# power_supply.net
KiCad netlist of a schematic drawn in Altium Designer
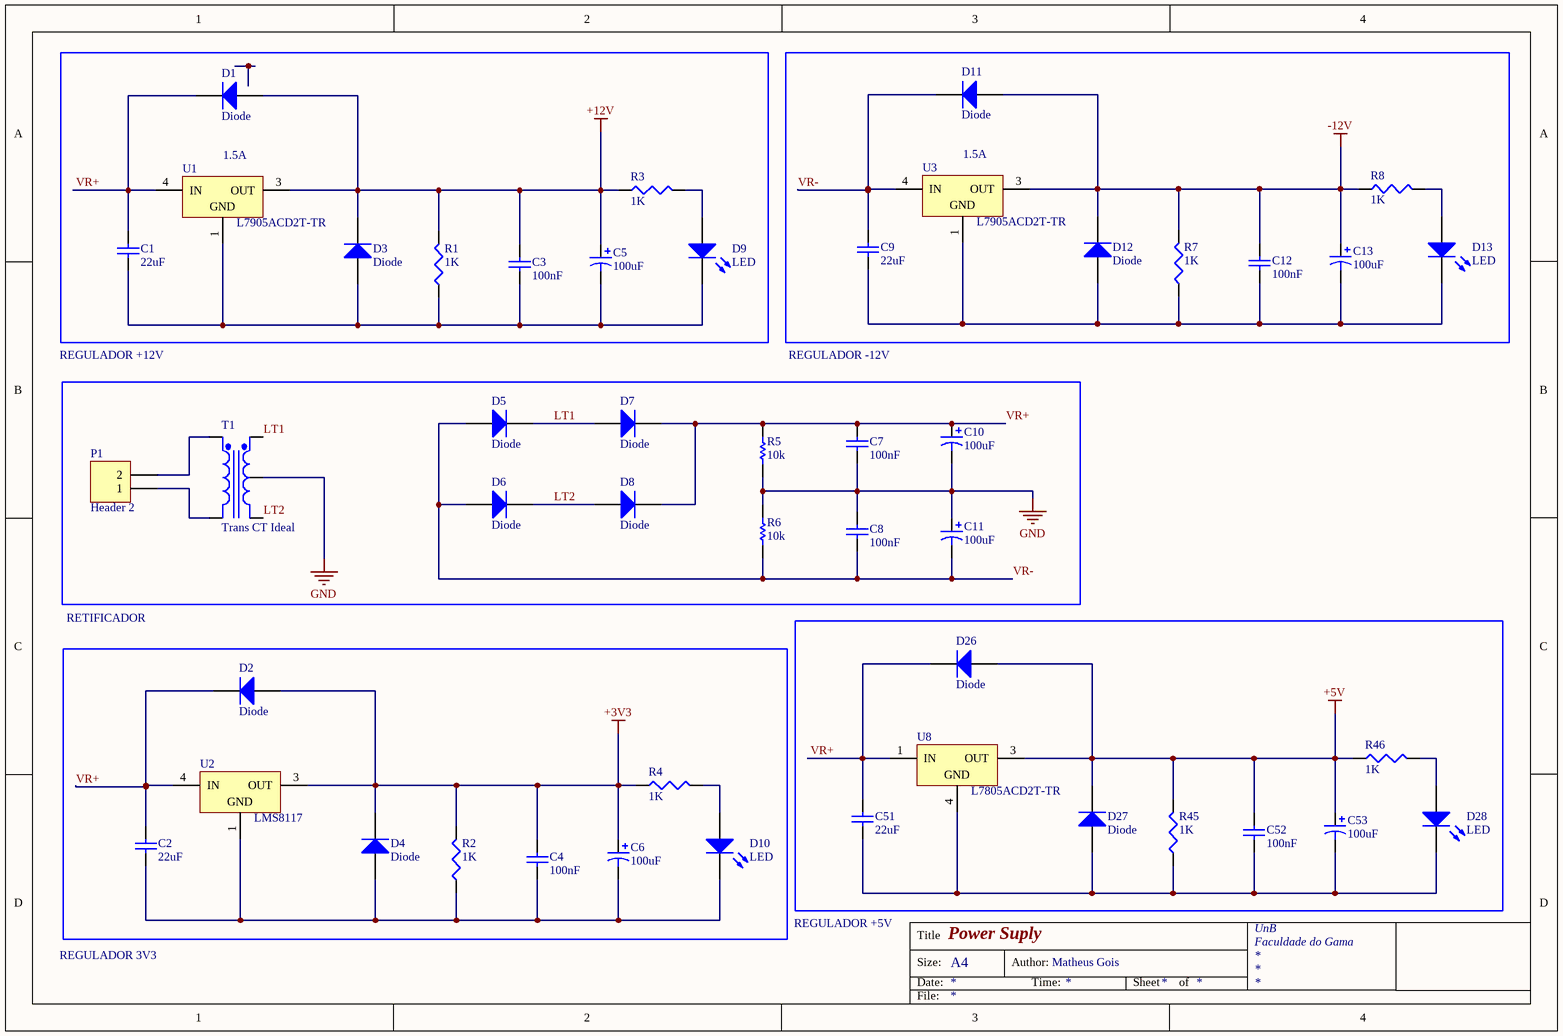
[diagram p0: power_supply.SchDoc]

(export (version "E")
  (design (tool "Eeschema 10.0.6"))
  (components
    (comp (ref "C1")
      (value "22uF")
      (footprint "C0603[0201]")
      (description "Cap Aluminum Polymer 22uF 20VDC 20% (6.3 X 5.9mm) SMD 0.06 Ohm 1450mA 5000h 105C T/R")
      (fields (field (name "MANUFACTURER PART NUMBER") "20SVPS22M") (field (name "TOLERANCE") "20%"))
      (libsource (lib "Basic Library") (part "C"))
    )
    (comp (ref "C2")
      (value "22uF")
      (footprint "C0603[0201]")
      (description "Cap Aluminum Polymer 22uF 20VDC 20% (6.3 X 5.9mm) SMD 0.06 Ohm 1450mA 5000h 105C T/R")
      (fields (field (name "MANUFACTURER PART NUMBER") "20SVPS22M") (field (name "TOLERANCE") "20%"))
      (libsource (lib "Basic Library") (part "C"))
    )
    (comp (ref "C3")
      (value "100nF")
      (footprint "C0603[0201]")
      (description "贴片陶瓷电容 0.1uF ±10% 50V X7R 0603")
      (fields (field (name "MANUFACTURER PART NUMBER") "C0603C104K5RACTU") (field (name "TOLERANCE") "10%"))
      (libsource (lib "Basic Library") (part "C"))
    )
    (comp (ref "C4")
      (value "100nF")
      (footprint "C0603[0201]")
      (description "贴片陶瓷电容 0.1uF ±10% 50V X7R 0603")
      (fields (field (name "MANUFACTURER PART NUMBER") "C0603C104K5RACTU") (field (name "TOLERANCE") "10%"))
      (libsource (lib "Basic Library") (part "C"))
    )
    (comp (ref "C5")
      (value "100uF")
      (footprint "Cap_Al_SMD_C6_6.6x6.6mm")
      (fields
        (field (name "MANUFACTURER PART NUMBER") "EMZA250ADA101MF80G")
        (field (name "TOLERANCE") "20%")
        (field (name "VOLTAGE") "25V")
      )
      (libsource (lib "Basic Library") (part "CP"))
    )
    (comp (ref "C6")
      (value "100uF")
      (footprint "Cap_Al_SMD_C6_6.6x6.6mm")
      (fields
        (field (name "MANUFACTURER PART NUMBER") "EMZA250ADA101MF80G")
        (field (name "TOLERANCE") "20%")
        (field (name "VOLTAGE") "25V")
      )
      (libsource (lib "Basic Library") (part "CP"))
    )
    (comp (ref "C7")
      (value "100nF")
      (footprint "C0603[0201]")
      (description "贴片陶瓷电容 0.1uF ±10% 50V X7R 0603")
      (fields (field (name "MANUFACTURER PART NUMBER") "C0603C104K5RACTU") (field (name "TOLERANCE") "10%"))
      (libsource (lib "Basic Library") (part "C"))
    )
    (comp (ref "C8")
      (value "100nF")
      (footprint "C0603[0201]")
      (description "贴片陶瓷电容 0.1uF ±10% 50V X7R 0603")
      (fields (field (name "MANUFACTURER PART NUMBER") "C0603C104K5RACTU") (field (name "TOLERANCE") "10%"))
      (libsource (lib "Basic Library") (part "C"))
    )
    (comp (ref "C9")
      (value "22uF")
      (footprint "C0603[0201]")
      (description "Cap Aluminum Polymer 22uF 20VDC 20% (6.3 X 5.9mm) SMD 0.06 Ohm 1450mA 5000h 105C T/R")
      (fields (field (name "MANUFACTURER PART NUMBER") "20SVPS22M") (field (name "TOLERANCE") "20%"))
      (libsource (lib "Basic Library") (part "C"))
    )
    (comp (ref "C10")
      (value "100uF")
      (footprint "Cap_Al_SMD_C6_6.6x6.6mm")
      (fields
        (field (name "MANUFACTURER PART NUMBER") "EMZA250ADA101MF80G")
        (field (name "TOLERANCE") "20%")
        (field (name "VOLTAGE") "25V")
      )
      (libsource (lib "Basic Library") (part "CP"))
    )
    (comp (ref "C11")
      (value "100uF")
      (footprint "Cap_Al_SMD_C6_6.6x6.6mm")
      (fields
        (field (name "MANUFACTURER PART NUMBER") "EMZA250ADA101MF80G")
        (field (name "TOLERANCE") "20%")
        (field (name "VOLTAGE") "25V")
      )
      (libsource (lib "Basic Library") (part "CP"))
    )
    (comp (ref "C12")
      (value "100nF")
      (footprint "C0603[0201]")
      (description "贴片陶瓷电容 0.1uF ±10% 50V X7R 0603")
      (fields (field (name "MANUFACTURER PART NUMBER") "C0603C104K5RACTU") (field (name "TOLERANCE") "10%"))
      (libsource (lib "Basic Library") (part "C"))
    )
    (comp (ref "C13")
      (value "100uF")
      (footprint "Cap_Al_SMD_C6_6.6x6.6mm")
      (fields
        (field (name "MANUFACTURER PART NUMBER") "EMZA250ADA101MF80G")
        (field (name "TOLERANCE") "20%")
        (field (name "VOLTAGE") "25V")
      )
      (libsource (lib "Basic Library") (part "CP"))
    )
    (comp (ref "C51")
      (value "22uF")
      (footprint "C0603[0201]")
      (description "Cap Aluminum Polymer 22uF 20VDC 20% (6.3 X 5.9mm) SMD 0.06 Ohm 1450mA 5000h 105C T/R")
      (fields (field (name "MANUFACTURER PART NUMBER") "20SVPS22M") (field (name "TOLERANCE") "20%"))
      (libsource (lib "Basic Library") (part "C"))
    )
    (comp (ref "C52")
      (value "100nF")
      (footprint "C0603[0201]")
      (description "贴片陶瓷电容 0.1uF ±10% 50V X7R 0603")
      (fields (field (name "MANUFACTURER PART NUMBER") "C0603C104K5RACTU") (field (name "TOLERANCE") "10%"))
      (libsource (lib "Basic Library") (part "C"))
    )
    (comp (ref "C53")
      (value "100uF")
      (footprint "Cap_Al_SMD_C6_6.6x6.6mm")
      (fields
        (field (name "MANUFACTURER PART NUMBER") "EMZA250ADA101MF80G")
        (field (name "TOLERANCE") "20%")
        (field (name "VOLTAGE") "25V")
      )
      (libsource (lib "Basic Library") (part "CP"))
    )
    (comp (ref "D1")
      (value "Diode")
      (footprint "SMC")
      (description "VR=100V IF=200mA")
      (fields
        (field (name "MANUFACTURER") "ON Semiconductor / Fairchild")
        (field (name "MANUFACTURER PART NUMBER") "FDLL4148")
        (field (name "PUBLISHER") "Altium Limited")
      )
      (libsource (lib "Miscellaneous Devices") (part "Diode"))
    )
    (comp (ref "D2")
      (value "Diode")
      (footprint "SMC")
      (description "VR=100V IF=200mA")
      (fields
        (field (name "MANUFACTURER") "ON Semiconductor / Fairchild")
        (field (name "MANUFACTURER PART NUMBER") "FDLL4148")
        (field (name "PUBLISHER") "Altium Limited")
      )
      (libsource (lib "Miscellaneous Devices") (part "Diode"))
    )
    (comp (ref "D3")
      (value "Diode")
      (footprint "SMC")
      (description "Standard Rectifier 1000V SOD-123")
      (fields
        (field (name "MANUFACTURER") "Sangdest Microelectronics")
        (field (name "MANUFACTURER PART NUMBER") "1N4007FLTR")
        (field (name "PUBLISHER") "Altium Limited")
      )
      (libsource (lib "Miscellaneous Devices") (part "Diode"))
    )
    (comp (ref "D4")
      (value "Diode")
      (footprint "SMC")
      (description "Standard Rectifier 1000V SOD-123")
      (fields
        (field (name "MANUFACTURER") "Sangdest Microelectronics")
        (field (name "MANUFACTURER PART NUMBER") "1N4007FLTR")
        (field (name "PUBLISHER") "Altium Limited")
      )
      (libsource (lib "Miscellaneous Devices") (part "Diode"))
    )
    (comp (ref "D5")
      (value "Diode")
      (footprint "SMC")
      (description "Standard Rectifier 1000V SOD-123")
      (fields
        (field (name "MANUFACTURER") "Sangdest Microelectronics")
        (field (name "MANUFACTURER PART NUMBER") "1N4007FLTR")
        (field (name "PUBLISHER") "Altium Limited")
      )
      (libsource (lib "Miscellaneous Devices") (part "Diode"))
    )
    (comp (ref "D6")
      (value "Diode")
      (footprint "SMC")
      (description "Standard Rectifier 1000V SOD-123")
      (fields
        (field (name "MANUFACTURER") "Sangdest Microelectronics")
        (field (name "MANUFACTURER PART NUMBER") "1N4007FLTR")
        (field (name "PUBLISHER") "Altium Limited")
      )
      (libsource (lib "Miscellaneous Devices") (part "Diode"))
    )
    (comp (ref "D7")
      (value "Diode")
      (footprint "SMC")
      (description "Standard Rectifier 1000V SOD-123")
      (fields
        (field (name "MANUFACTURER") "Sangdest Microelectronics")
        (field (name "MANUFACTURER PART NUMBER") "1N4007FLTR")
        (field (name "PUBLISHER") "Altium Limited")
      )
      (libsource (lib "Miscellaneous Devices") (part "Diode"))
    )
    (comp (ref "D8")
      (value "Diode")
      (footprint "SMC")
      (description "Standard Rectifier 1000V SOD-123")
      (fields
        (field (name "MANUFACTURER") "Sangdest Microelectronics")
        (field (name "MANUFACTURER PART NUMBER") "1N4007FLTR")
        (field (name "PUBLISHER") "Altium Limited")
      )
      (libsource (lib "Miscellaneous Devices") (part "Diode"))
    )
    (comp (ref "D9")
      (value "LED")
      (footprint "LED-0603-G")
      (description "0603(H=0.9mm) 绿色 λD=569nm VR=5V VF=2.1V~2.6V IF=20mA PD=100mW")
      (fields (field (name "MANUFACTURER PART NUMBER") "LTST-C190GKT") (field (name "VOLTAGE") "2V"))
      (libsource (lib "Basic Library") (part "LED"))
    )
    (comp (ref "D10")
      (value "LED")
      (footprint "LED-0603-G")
      (description "0603(H=0.9mm) 绿色 λD=569nm VR=5V VF=2.1V~2.6V IF=20mA PD=100mW")
      (fields (field (name "MANUFACTURER PART NUMBER") "LTST-C190GKT") (field (name "VOLTAGE") "2V"))
      (libsource (lib "Basic Library") (part "LED"))
    )
    (comp (ref "D11")
      (value "Diode")
      (footprint "SMC")
      (description "VR=100V IF=200mA")
      (fields
        (field (name "MANUFACTURER") "ON Semiconductor / Fairchild")
        (field (name "MANUFACTURER PART NUMBER") "FDLL4148")
        (field (name "PUBLISHER") "Altium Limited")
      )
      (libsource (lib "Miscellaneous Devices") (part "Diode"))
    )
    (comp (ref "D12")
      (value "Diode")
      (footprint "SMC")
      (description "Standard Rectifier 1000V SOD-123")
      (fields
        (field (name "MANUFACTURER") "Sangdest Microelectronics")
        (field (name "MANUFACTURER PART NUMBER") "1N4007FLTR")
        (field (name "PUBLISHER") "Altium Limited")
      )
      (libsource (lib "Miscellaneous Devices") (part "Diode"))
    )
    (comp (ref "D13")
      (value "LED")
      (footprint "LED-0603-G")
      (description "0603(H=0.9mm) 绿色 λD=569nm VR=5V VF=2.1V~2.6V IF=20mA PD=100mW")
      (fields (field (name "MANUFACTURER PART NUMBER") "LTST-C190GKT") (field (name "VOLTAGE") "2V"))
      (libsource (lib "Basic Library") (part "LED"))
    )
    (comp (ref "D26")
      (value "Diode")
      (footprint "SMC")
      (description "VR=100V IF=200mA")
      (fields
        (field (name "MANUFACTURER") "ON Semiconductor / Fairchild")
        (field (name "MANUFACTURER PART NUMBER") "FDLL4148")
        (field (name "PUBLISHER") "Altium Limited")
      )
      (libsource (lib "Miscellaneous Devices") (part "Diode"))
    )
    (comp (ref "D27")
      (value "Diode")
      (footprint "SMC")
      (description "Standard Rectifier 1000V SOD-123")
      (fields
        (field (name "MANUFACTURER") "Sangdest Microelectronics")
        (field (name "MANUFACTURER PART NUMBER") "1N4007FLTR")
        (field (name "PUBLISHER") "Altium Limited")
      )
      (libsource (lib "Miscellaneous Devices") (part "Diode"))
    )
    (comp (ref "D28")
      (value "LED")
      (footprint "LED-0603-G")
      (description "0603(H=0.9mm) 绿色 λD=569nm VR=5V VF=2.1V~2.6V IF=20mA PD=100mW")
      (fields (field (name "MANUFACTURER PART NUMBER") "LTST-C190GKT") (field (name "VOLTAGE") "2V"))
      (libsource (lib "Basic Library") (part "LED"))
    )
    (comp (ref "P1")
      (value "Header 2")
      (footprint "HDR1X2")
      (description "间距5.08mm 2pin 母座 12A 320V 弯插 封边")
      (fields
        (field (name "MANUFACTURER") "Phoenix Contact")
        (field (name "MANUFACTURER PART NUMBER") "1757242")
        (field (name "PUBLISHER") "Altium Limited")
      )
      (libsource (lib "Miscellaneous Connectors") (part "Header 2"))
    )
    (comp (ref "R1")
      (value "1K")
      (footprint "RESC6332")
      (description "Res Metal Strip 1206 0.001 Ohm 1% 0.25W(1/4W) ±275ppm/C Sulfur Resistant Pad SMD Automotive T/R")
      (fields
        (field (name "MANUFACTURER") "Vishay")
        (field (name "MANUFACTURER PART NUMBER") "WSL12061L000FEA")
        (field (name "PUBLISHER") "Altium Limited")
      )
      (libsource (lib "Miscellaneous Devices") (part "Res3"))
    )
    (comp (ref "R2")
      (value "1K")
      (footprint "RESC6332")
      (description "Res Metal Strip 1206 0.001 Ohm 1% 0.25W(1/4W) ±275ppm/C Sulfur Resistant Pad SMD Automotive T/R")
      (fields
        (field (name "MANUFACTURER") "Vishay")
        (field (name "MANUFACTURER PART NUMBER") "WSL12061L000FEA")
        (field (name "PUBLISHER") "Altium Limited")
      )
      (libsource (lib "Miscellaneous Devices") (part "Res3"))
    )
    (comp (ref "R3")
      (value "1K")
      (footprint "12Z-2010")
      (description "Res Metal Strip 1206 0.001 Ohm 1% 0.25W(1/4W) ±275ppm/C Sulfur Resistant Pad SMD Automotive T/R")
      (fields
        (field (name "MANUFACTURER") "Vishay")
        (field (name "MANUFACTURER PART NUMBER") "WSL12061L000FEA")
        (field (name "PUBLISHER") "Altium Limited")
      )
      (libsource (lib "Miscellaneous Devices") (part "Res3"))
    )
    (comp (ref "R4")
      (value "1K")
      (footprint "12Z-2010")
      (description "Res Metal Strip 1206 0.001 Ohm 1% 0.25W(1/4W) ±275ppm/C Sulfur Resistant Pad SMD Automotive T/R")
      (fields
        (field (name "MANUFACTURER") "Vishay")
        (field (name "MANUFACTURER PART NUMBER") "WSL12061L000FEA")
        (field (name "PUBLISHER") "Altium Limited")
      )
      (libsource (lib "Miscellaneous Devices") (part "Res3"))
    )
    (comp (ref "R5")
      (value "10k")
      (footprint "R1608[0603]")
      (description "Res, 10K, 0.01%, 0.25W, 1206, Metal Foil")
      (fields (field (name "MANUFACTURER PART NUMBER") "Y163010K0000T9R") (field (name "TOLERANCE") "0.01%"))
      (libsource (lib "Basic Library") (part "R"))
    )
    (comp (ref "R6")
      (value "10k")
      (footprint "R1608[0603]")
      (description "Res, 10K, 0.01%, 0.25W, 1206, Metal Foil")
      (fields (field (name "MANUFACTURER PART NUMBER") "Y163010K0000T9R") (field (name "TOLERANCE") "0.01%"))
      (libsource (lib "Basic Library") (part "R"))
    )
    (comp (ref "R7")
      (value "1K")
      (footprint "RESC6332")
      (description "Res Metal Strip 1206 0.001 Ohm 1% 0.25W(1/4W) ±275ppm/C Sulfur Resistant Pad SMD Automotive T/R")
      (fields
        (field (name "MANUFACTURER") "Vishay")
        (field (name "MANUFACTURER PART NUMBER") "WSL12061L000FEA")
        (field (name "PUBLISHER") "Altium Limited")
      )
      (libsource (lib "Miscellaneous Devices") (part "Res3"))
    )
    (comp (ref "R8")
      (value "1K")
      (footprint "12Z-2010")
      (description "Res Metal Strip 1206 0.001 Ohm 1% 0.25W(1/4W) ±275ppm/C Sulfur Resistant Pad SMD Automotive T/R")
      (fields
        (field (name "MANUFACTURER") "Vishay")
        (field (name "MANUFACTURER PART NUMBER") "WSL12061L000FEA")
        (field (name "PUBLISHER") "Altium Limited")
      )
      (libsource (lib "Miscellaneous Devices") (part "Res3"))
    )
    (comp (ref "R45")
      (value "1K")
      (footprint "RESC6332")
      (description "Res Metal Strip 1206 0.001 Ohm 1% 0.25W(1/4W) ±275ppm/C Sulfur Resistant Pad SMD Automotive T/R")
      (fields
        (field (name "MANUFACTURER") "Vishay")
        (field (name "MANUFACTURER PART NUMBER") "WSL12061L000FEA")
        (field (name "PUBLISHER") "Altium Limited")
      )
      (libsource (lib "Miscellaneous Devices") (part "Res3"))
    )
    (comp (ref "R46")
      (value "1K")
      (footprint "12Z-2010")
      (description "Res Metal Strip 1206 0.001 Ohm 1% 0.25W(1/4W) ±275ppm/C Sulfur Resistant Pad SMD Automotive T/R")
      (fields
        (field (name "MANUFACTURER") "Vishay")
        (field (name "MANUFACTURER PART NUMBER") "WSL12061L000FEA")
        (field (name "PUBLISHER") "Altium Limited")
      )
      (libsource (lib "Miscellaneous Devices") (part "Res3"))
    )
    (comp (ref "T1")
      (value "Trans CT Ideal")
      (description "Center-Tapped Transformer (Ideal)")
      (libsource (lib "Basic Library") (part "Trans CT Ideal"))
    )
    (comp (ref "U1")
      (value "L7905ACD2T-TR")
      (footprint "TO-263_N")
      (description "L7912 Series 1.5 A -12 V Fixed Output SMT Negative Voltage Regulator - D2PAK")
      (fields
        (field (name "MANUFACTURER") "STMicroelectronics")
        (field (name "MANUFACTURER PART NUMBER") "L7912CD2T-TR")
        (field (name "OUTPUT CURRENT") "1.5A")
      )
      (libsource (lib "STMicroelectronics Power Management Linear Regulator") (part "L7905ACD2T-TR"))
    )
    (comp (ref "U2")
      (value "LMS8117")
      (footprint "TO-263_N")
      (description "1-A, 15-V, linear voltage regulator from 0°C to 125°C 3-TO-252 0 to 125")
      (fields (field (name "PARTNUMBER") "L7905ACD2T-TR") (field (name "MANUFACTURER") "STMicroelectronics"))
      (libsource (lib "STMicroelectronics Power Management Linear Regulator") (part "L7905ACD2T-TR"))
    )
    (comp (ref "U3")
      (value "L7905ACD2T-TR")
      (footprint "TO-263_N")
      (description "L7912 Series 1.5 A -12 V Fixed Output SMT Negative Voltage Regulator - D2PAK")
      (fields
        (field (name "MANUFACTURER") "STMicroelectronics")
        (field (name "MANUFACTURER PART NUMBER") "L7912CD2T-TR")
        (field (name "OUTPUT CURRENT") "1.5A")
      )
      (libsource (lib "STMicroelectronics Power Management Linear Regulator") (part "L7905ACD2T-TR"))
    )
    (comp (ref "U8")
      (value "L7805ACD2T-TR")
      (footprint "TO-263_N")
      (description "Positive Voltage Regulator, 3-Pin D2PAK, Tape and Reel")
      (libsource (lib "STMicroelectronics Power Management Linear Regulator") (part "L7805ACD2T-TR"))
    )
  )
  (nets
    (net (code "1") (name "+3V3") (class "Default")
      (node (ref "C4") (pin "2") (pinfunction "2_2") (pintype "passive"))
      (node (ref "C6") (pin "1") (pinfunction "1_1") (pintype "passive"))
      (node (ref "D2") (pin "1") (pinfunction "A_1") (pintype "passive"))
      (node (ref "D4") (pin "2") (pinfunction "K_2") (pintype "passive"))
      (node (ref "R2") (pin "2") (pinfunction "2_2") (pintype "passive"))
      (node (ref "R4") (pin "1") (pinfunction "1_1") (pintype "passive"))
      (node (ref "U2") (pin "3") (pinfunction "OUT_3") (pintype "power_in"))
    )
    (net (code "2") (name "+5V") (class "Default")
      (node (ref "C52") (pin "2") (pinfunction "2_2") (pintype "passive"))
      (node (ref "C53") (pin "1") (pinfunction "1_1") (pintype "passive"))
      (node (ref "D26") (pin "1") (pinfunction "A_1") (pintype "passive"))
      (node (ref "D27") (pin "2") (pinfunction "K_2") (pintype "passive"))
      (node (ref "R45") (pin "2") (pinfunction "2_2") (pintype "passive"))
      (node (ref "R46") (pin "1") (pinfunction "1_1") (pintype "passive"))
      (node (ref "U8") (pin "3") (pinfunction "OUT_3") (pintype "power_in"))
    )
    (net (code "3") (name "+12V") (class "Default")
      (node (ref "C3") (pin "2") (pinfunction "2_2") (pintype "passive"))
      (node (ref "C5") (pin "1") (pinfunction "1_1") (pintype "passive"))
      (node (ref "D1") (pin "1") (pinfunction "A_1") (pintype "passive"))
      (node (ref "D3") (pin "2") (pinfunction "K_2") (pintype "passive"))
      (node (ref "R1") (pin "2") (pinfunction "2_2") (pintype "passive"))
      (node (ref "R3") (pin "1") (pinfunction "1_1") (pintype "passive"))
      (node (ref "U1") (pin "3") (pinfunction "OUT_3") (pintype "power_in"))
    )
    (net (code "4") (name "-12V") (class "Default")
      (node (ref "C12") (pin "2") (pinfunction "2_2") (pintype "passive"))
      (node (ref "C13") (pin "1") (pinfunction "1_1") (pintype "passive"))
      (node (ref "D11") (pin "1") (pinfunction "A_1") (pintype "passive"))
      (node (ref "D12") (pin "2") (pinfunction "K_2") (pintype "passive"))
      (node (ref "R7") (pin "2") (pinfunction "2_2") (pintype "passive"))
      (node (ref "R8") (pin "1") (pinfunction "1_1") (pintype "passive"))
      (node (ref "U3") (pin "3") (pinfunction "OUT_3") (pintype "power_in"))
    )
    (net (code "5") (name "/LT1") (class "Default")
      (node (ref "D5") (pin "2") (pinfunction "K_2") (pintype "passive"))
      (node (ref "D7") (pin "1") (pinfunction "A_1") (pintype "passive"))
      (node (ref "T1") (pin "3") (pinfunction "Sec+_3") (pintype "passive"))
    )
    (net (code "6") (name "/LT2") (class "Default")
      (node (ref "D6") (pin "2") (pinfunction "K_2") (pintype "passive"))
      (node (ref "D8") (pin "1") (pinfunction "A_1") (pintype "passive"))
      (node (ref "T1") (pin "5") (pinfunction "Sec-_5") (pintype "passive"))
    )
    (net (code "7") (name "/VR+") (class "Default")
      (node (ref "C1") (pin "2") (pinfunction "2_2") (pintype "passive"))
      (node (ref "C10") (pin "1") (pinfunction "1_1") (pintype "passive"))
      (node (ref "C2") (pin "2") (pinfunction "2_2") (pintype "passive"))
      (node (ref "C51") (pin "2") (pinfunction "2_2") (pintype "passive"))
      (node (ref "C7") (pin "2") (pinfunction "2_2") (pintype "passive"))
      (node (ref "D1") (pin "2") (pinfunction "K_2") (pintype "passive"))
      (node (ref "D2") (pin "2") (pinfunction "K_2") (pintype "passive"))
      (node (ref "D26") (pin "2") (pinfunction "K_2") (pintype "passive"))
      (node (ref "D7") (pin "2") (pinfunction "K_2") (pintype "passive"))
      (node (ref "D8") (pin "2") (pinfunction "K_2") (pintype "passive"))
      (node (ref "R5") (pin "2") (pinfunction "2_2") (pintype "passive"))
      (node (ref "U1") (pin "4") (pinfunction "IN_4") (pintype "power_in"))
      (node (ref "U2") (pin "4") (pinfunction "IN_4") (pintype "power_in"))
      (node (ref "U8") (pin "1") (pinfunction "IN_1") (pintype "power_in"))
    )
    (net (code "8") (name "/VR-") (class "Default")
      (node (ref "C11") (pin "2") (pinfunction "2_2") (pintype "passive"))
      (node (ref "C8") (pin "1") (pinfunction "1_1") (pintype "passive"))
      (node (ref "C9") (pin "2") (pinfunction "2_2") (pintype "passive"))
      (node (ref "D11") (pin "2") (pinfunction "K_2") (pintype "passive"))
      (node (ref "D5") (pin "1") (pinfunction "A_1") (pintype "passive"))
      (node (ref "D6") (pin "1") (pinfunction "A_1") (pintype "passive"))
      (node (ref "R6") (pin "1") (pinfunction "1_1") (pintype "passive"))
      (node (ref "U3") (pin "4") (pinfunction "IN_4") (pintype "power_in"))
    )
    (net (code "9") (name "GND") (class "Default")
      (node (ref "C10") (pin "2") (pinfunction "2_2") (pintype "passive"))
      (node (ref "C11") (pin "1") (pinfunction "1_1") (pintype "passive"))
      (node (ref "C7") (pin "1") (pinfunction "1_1") (pintype "passive"))
      (node (ref "C8") (pin "2") (pinfunction "2_2") (pintype "passive"))
      (node (ref "R5") (pin "1") (pinfunction "1_1") (pintype "passive"))
      (node (ref "R6") (pin "2") (pinfunction "2_2") (pintype "passive"))
      (node (ref "T1") (pin "4") (pinfunction "SecCT_4") (pintype "passive"))
    )
    (net (code "10") (name "Net-(D3-A)") (class "Default")
      (node (ref "C1") (pin "1") (pinfunction "1_1") (pintype "passive"))
      (node (ref "C3") (pin "1") (pinfunction "1_1") (pintype "passive"))
      (node (ref "C5") (pin "2") (pinfunction "2_2") (pintype "passive"))
      (node (ref "D3") (pin "1") (pinfunction "A_1") (pintype "passive"))
      (node (ref "D9") (pin "2") (pinfunction "K_2") (pintype "passive"))
      (node (ref "R1") (pin "1") (pinfunction "1_1") (pintype "passive"))
      (node (ref "U1") (pin "1") (pinfunction "GND_1") (pintype "power_in"))
    )
    (net (code "11") (name "Net-(D9-A)") (class "Default")
      (node (ref "D9") (pin "1") (pinfunction "A_1") (pintype "passive"))
      (node (ref "R3") (pin "2") (pinfunction "2_2") (pintype "passive"))
    )
    (net (code "12") (name "Net-(D10-A)") (class "Default")
      (node (ref "D10") (pin "1") (pinfunction "A_1") (pintype "passive"))
      (node (ref "R4") (pin "2") (pinfunction "2_2") (pintype "passive"))
    )
    (net (code "13") (name "Net-(D10-K)") (class "Default")
      (node (ref "C2") (pin "1") (pinfunction "1_1") (pintype "passive"))
      (node (ref "C4") (pin "1") (pinfunction "1_1") (pintype "passive"))
      (node (ref "C6") (pin "2") (pinfunction "2_2") (pintype "passive"))
      (node (ref "D10") (pin "2") (pinfunction "K_2") (pintype "passive"))
      (node (ref "D4") (pin "1") (pinfunction "A_1") (pintype "passive"))
      (node (ref "R2") (pin "1") (pinfunction "1_1") (pintype "passive"))
      (node (ref "U2") (pin "1") (pinfunction "GND_1") (pintype "power_in"))
    )
    (net (code "14") (name "Net-(D12-A)") (class "Default")
      (node (ref "C12") (pin "1") (pinfunction "1_1") (pintype "passive"))
      (node (ref "C13") (pin "2") (pinfunction "2_2") (pintype "passive"))
      (node (ref "C9") (pin "1") (pinfunction "1_1") (pintype "passive"))
      (node (ref "D12") (pin "1") (pinfunction "A_1") (pintype "passive"))
      (node (ref "D13") (pin "2") (pinfunction "K_2") (pintype "passive"))
      (node (ref "R7") (pin "1") (pinfunction "1_1") (pintype "passive"))
      (node (ref "U3") (pin "1") (pinfunction "GND_1") (pintype "power_in"))
    )
    (net (code "15") (name "Net-(D13-A)") (class "Default")
      (node (ref "D13") (pin "1") (pinfunction "A_1") (pintype "passive"))
      (node (ref "R8") (pin "2") (pinfunction "2_2") (pintype "passive"))
    )
    (net (code "16") (name "Net-(D27-A)") (class "Default")
      (node (ref "C51") (pin "1") (pinfunction "1_1") (pintype "passive"))
      (node (ref "C52") (pin "1") (pinfunction "1_1") (pintype "passive"))
      (node (ref "C53") (pin "2") (pinfunction "2_2") (pintype "passive"))
      (node (ref "D27") (pin "1") (pinfunction "A_1") (pintype "passive"))
      (node (ref "D28") (pin "2") (pinfunction "K_2") (pintype "passive"))
      (node (ref "R45") (pin "1") (pinfunction "1_1") (pintype "passive"))
      (node (ref "U8") (pin "4") (pinfunction "GND_4") (pintype "power_in"))
    )
    (net (code "17") (name "Net-(D28-A)") (class "Default")
      (node (ref "D28") (pin "1") (pinfunction "A_1") (pintype "passive"))
      (node (ref "R46") (pin "2") (pinfunction "2_2") (pintype "passive"))
    )
    (net (code "18") (name "Net-(T1-Pri+)") (class "Default")
      (node (ref "P1") (pin "2") (pinfunction "2_2") (pintype "passive"))
      (node (ref "T1") (pin "1") (pinfunction "Pri+_1") (pintype "passive"))
    )
    (net (code "19") (name "Net-(T1-Pri-)") (class "Default")
      (node (ref "P1") (pin "1") (pinfunction "1_1") (pintype "passive"))
      (node (ref "T1") (pin "2") (pinfunction "Pri-_2") (pintype "passive"))
    )
  )
)
